# Retrokit_SAMD_RevA.net
KiCad netlist of a schematic drawn in EAGLE
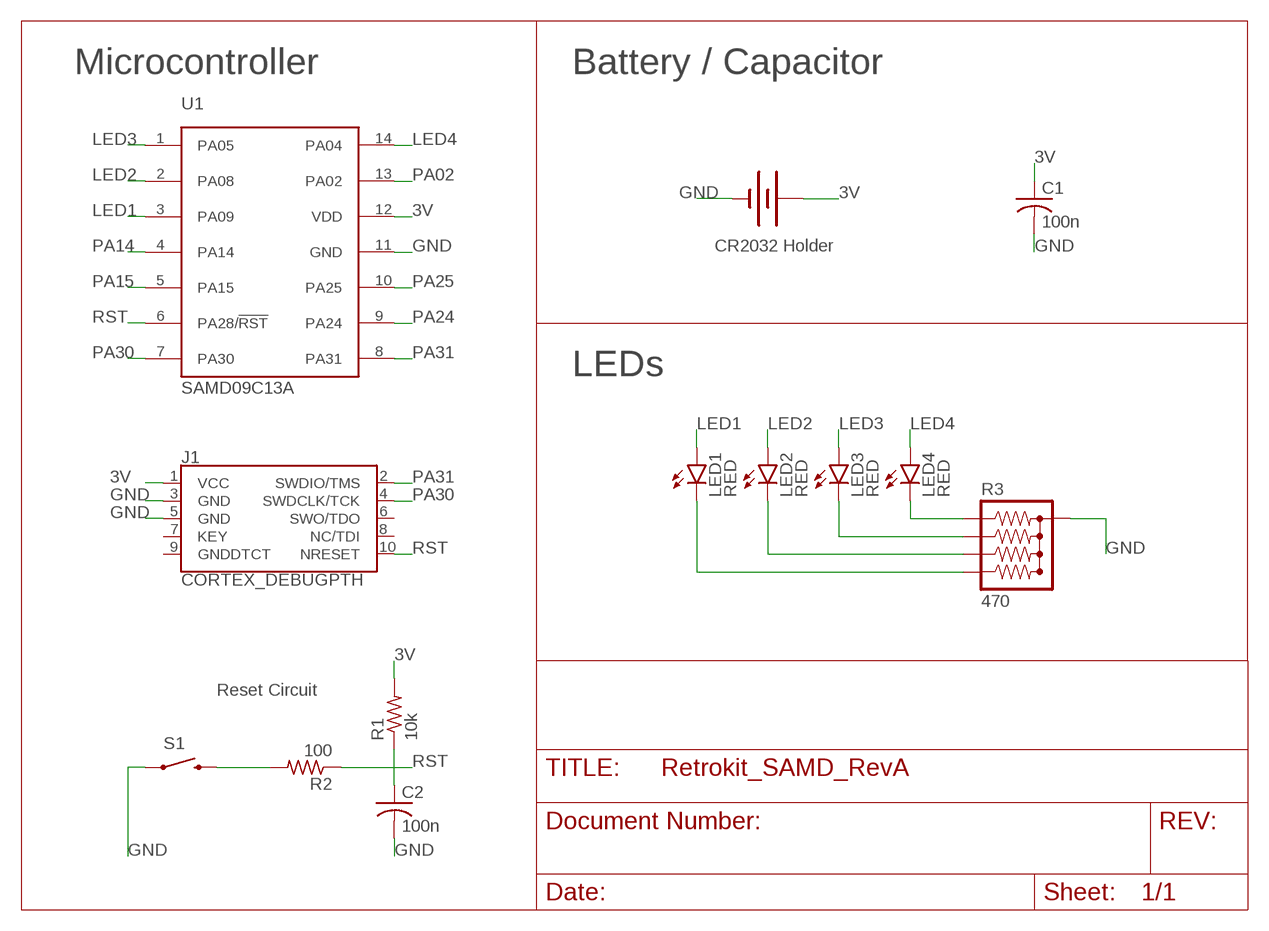
[diagram p0: schematic, sheet 1]

(export (version "E")
  (design (tool "Eeschema 10.0.6"))
  (components
    (comp (ref "BAT1")
      (value "BATTERYFOB")
      (footprint "eagle-import:BATTERY_20MM_PTH_COMPACT")
      (libsource (lib "eagle-import") (part "BATTERYFOB"))
    )
    (comp (ref "C1")
      (value "100n")
      (footprint "eagle-import:C025-024X044")
      (libsource (lib "eagle-import") (part "C-US025-024X044"))
    )
    (comp (ref "C2")
      (value "100n")
      (footprint "eagle-import:C0805")
      (libsource (lib "eagle-import") (part "C-USC0805"))
    )
    (comp (ref "J1")
      (value "CORTEX_DEBUGPTH")
      (footprint "eagle-import:2X5-PTH-1.27MM")
      (libsource (lib "eagle-import") (part "CORTEX_DEBUGPTH"))
    )
    (comp (ref "LED1")
      (value "RED")
      (footprint "eagle-import:LED3MM")
      (libsource (lib "eagle-import") (part "LED3MM"))
    )
    (comp (ref "LED2")
      (value "RED")
      (footprint "eagle-import:LED3MM")
      (libsource (lib "eagle-import") (part "LED3MM"))
    )
    (comp (ref "LED3")
      (value "RED")
      (footprint "eagle-import:LED3MM")
      (libsource (lib "eagle-import") (part "LED3MM"))
    )
    (comp (ref "LED4")
      (value "RED")
      (footprint "eagle-import:LED3MM")
      (libsource (lib "eagle-import") (part "LED3MM"))
    )
    (comp (ref "R1")
      (value "10k")
      (footprint "eagle-import:R0805")
      (libsource (lib "eagle-import") (part "R-US_R0805"))
    )
    (comp (ref "R2")
      (value "100")
      (footprint "eagle-import:R0805")
      (libsource (lib "eagle-import") (part "R-US_R0805"))
    )
    (comp (ref "R3")
      (value "470")
      (footprint "eagle-import:RBUSSED-5SIP")
      (libsource (lib "eagle-import") (part "RBUSSED-5SIP"))
    )
    (comp (ref "S1")
      (value "SWITCH-MOMENTARY-2PTH")
      (footprint "eagle-import:TACTILE-PTH")
      (libsource (lib "eagle-import") (part "SWITCH-MOMENTARY-2PTH"))
    )
    (comp (ref "U1")
      (value "SAMD09C13A")
      (footprint "eagle-import:SO14-NARROWPADS")
      (libsource (lib "eagle-import") (part "SAMD09C13A"))
    )
  )
  (nets
    (net (code "1") (name "/3V") (class "Default")
      (node (ref "BAT1") (pin "1") (pinfunction "+_1") (pintype "power_in"))
      (node (ref "C1") (pin "1") (pinfunction "1_1") (pintype "passive"))
      (node (ref "J1") (pin "1") (pinfunction "VCC_1") (pintype "bidirectional"))
      (node (ref "R1") (pin "2") (pinfunction "2_2") (pintype "passive"))
      (node (ref "U1") (pin "12") (pinfunction "VDD_12") (pintype "bidirectional"))
    )
    (net (code "2") (name "/GND") (class "Default")
      (node (ref "BAT1") (pin "2") (pinfunction "-_2") (pintype "power_in"))
      (node (ref "C1") (pin "2") (pinfunction "2_2") (pintype "passive"))
      (node (ref "C2") (pin "2") (pinfunction "2_2") (pintype "passive"))
      (node (ref "J1") (pin "3") (pinfunction "GND_3") (pintype "bidirectional"))
      (node (ref "J1") (pin "5") (pinfunction "GND_5") (pintype "bidirectional"))
      (node (ref "R3") (pin "GND") (pinfunction "GND_GND") (pintype "passive"))
      (node (ref "S1") (pin "1") (pinfunction "1_1") (pintype "passive"))
      (node (ref "U1") (pin "11") (pinfunction "GND_11") (pintype "bidirectional"))
    )
    (net (code "3") (name "/LED1") (class "Default")
      (node (ref "LED1") (pin "A") (pinfunction "A_A") (pintype "passive"))
      (node (ref "U1") (pin "3") (pinfunction "PA09_3") (pintype "bidirectional"))
    )
    (net (code "4") (name "/LED2") (class "Default")
      (node (ref "LED2") (pin "A") (pinfunction "A_A") (pintype "passive"))
      (node (ref "U1") (pin "2") (pinfunction "PA08_2") (pintype "bidirectional"))
    )
    (net (code "5") (name "/LED3") (class "Default")
      (node (ref "LED3") (pin "A") (pinfunction "A_A") (pintype "passive"))
      (node (ref "U1") (pin "1") (pinfunction "PA05_1") (pintype "bidirectional"))
    )
    (net (code "6") (name "/LED4") (class "Default")
      (node (ref "LED4") (pin "A") (pinfunction "A_A") (pintype "passive"))
      (node (ref "U1") (pin "14") (pinfunction "PA04_14") (pintype "bidirectional"))
    )
    (net (code "7") (name "/PA02") (class "Default")
      (node (ref "U1") (pin "13") (pinfunction "PA02_13") (pintype "bidirectional"))
    )
    (net (code "8") (name "/PA14") (class "Default")
      (node (ref "U1") (pin "4") (pinfunction "PA14_4") (pintype "bidirectional"))
    )
    (net (code "9") (name "/PA15") (class "Default")
      (node (ref "U1") (pin "5") (pinfunction "PA15_5") (pintype "bidirectional"))
    )
    (net (code "10") (name "/PA24") (class "Default")
      (node (ref "U1") (pin "9") (pinfunction "PA24_9") (pintype "bidirectional"))
    )
    (net (code "11") (name "/PA25") (class "Default")
      (node (ref "U1") (pin "10") (pinfunction "PA25_10") (pintype "bidirectional"))
    )
    (net (code "12") (name "/PA30") (class "Default")
      (node (ref "J1") (pin "4") (pinfunction "SWDCLK/TCK_4") (pintype "bidirectional"))
      (node (ref "U1") (pin "7") (pinfunction "PA30_7") (pintype "bidirectional"))
    )
    (net (code "13") (name "/PA31") (class "Default")
      (node (ref "J1") (pin "2") (pinfunction "SWDIO/TMS_2") (pintype "bidirectional"))
      (node (ref "U1") (pin "8") (pinfunction "PA31_8") (pintype "bidirectional"))
    )
    (net (code "14") (name "/RST") (class "Default")
      (node (ref "C2") (pin "1") (pinfunction "1_1") (pintype "passive"))
      (node (ref "J1") (pin "10") (pinfunction "NRESET_10") (pintype "bidirectional"))
      (node (ref "R1") (pin "1") (pinfunction "1_1") (pintype "passive"))
      (node (ref "R2") (pin "1") (pinfunction "1_1") (pintype "passive"))
      (node (ref "U1") (pin "6") (pinfunction "PA28/~{RST}_6") (pintype "bidirectional"))
    )
    (net (code "15") (name "Net-(LED1-C)") (class "Default")
      (node (ref "LED1") (pin "K") (pinfunction "C_K") (pintype "passive"))
      (node (ref "R3") (pin "R4") (pinfunction "R4_R4") (pintype "passive"))
    )
    (net (code "16") (name "Net-(LED2-C)") (class "Default")
      (node (ref "LED2") (pin "K") (pinfunction "C_K") (pintype "passive"))
      (node (ref "R3") (pin "R3") (pinfunction "R3_R3") (pintype "passive"))
    )
    (net (code "17") (name "Net-(LED3-C)") (class "Default")
      (node (ref "LED3") (pin "K") (pinfunction "C_K") (pintype "passive"))
      (node (ref "R3") (pin "R2") (pinfunction "R2_R2") (pintype "passive"))
    )
    (net (code "18") (name "Net-(LED4-C)") (class "Default")
      (node (ref "LED4") (pin "K") (pinfunction "C_K") (pintype "passive"))
      (node (ref "R3") (pin "R1") (pinfunction "R1_R1") (pintype "passive"))
    )
    (net (code "19") (name "Net-(S1-2)") (class "Default")
      (node (ref "R2") (pin "2") (pinfunction "2_2") (pintype "passive"))
      (node (ref "S1") (pin "3") (pinfunction "2_3") (pintype "passive"))
    )
    (net (code "20") (name "unconnected-(J1-GNDDTCT-Pad9)") (class "Default")
      (node (ref "J1") (pin "9") (pinfunction "GNDDTCT_9") (pintype "bidirectional"))
    )
    (net (code "21") (name "unconnected-(J1-KEY-Pad7)") (class "Default")
      (node (ref "J1") (pin "7") (pinfunction "KEY_7") (pintype "bidirectional"))
    )
    (net (code "22") (name "unconnected-(J1-NC{slash}TDI-Pad8)") (class "Default")
      (node (ref "J1") (pin "8") (pinfunction "NC/TDI_8") (pintype "bidirectional"))
    )
    (net (code "23") (name "unconnected-(J1-SWO{slash}TDO-Pad6)") (class "Default")
      (node (ref "J1") (pin "6") (pinfunction "SWO/TDO_6") (pintype "bidirectional"))
    )
  )
)
